# U_WE_BOX.net
KiCad netlist of a schematic drawn in EAGLE
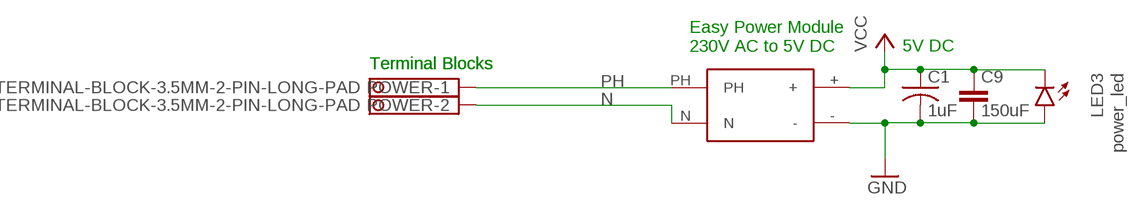
[diagram p0: schematic, sheet 1]
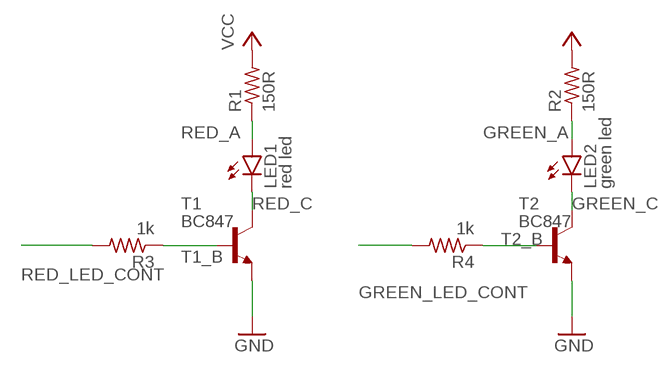
[diagram p1: schematic, sheet 2]
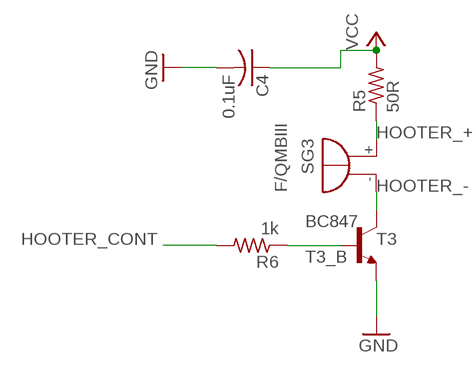
[diagram p2: schematic, sheet 3]
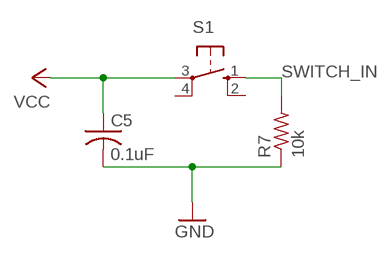
[diagram p3: schematic, sheet 4]
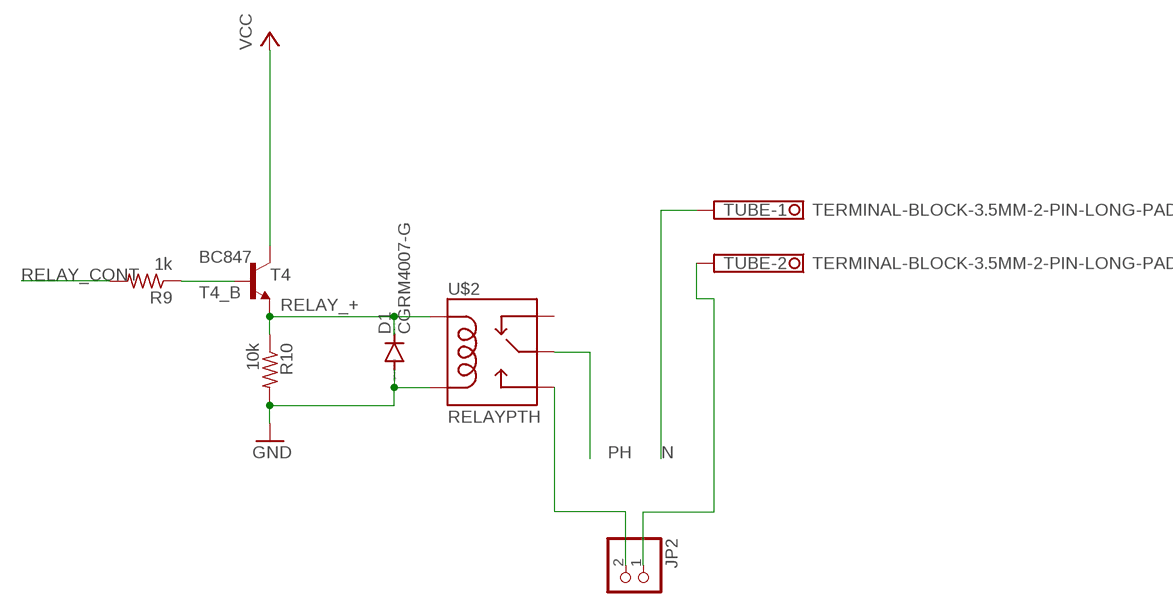
[diagram p4: schematic, sheet 5]
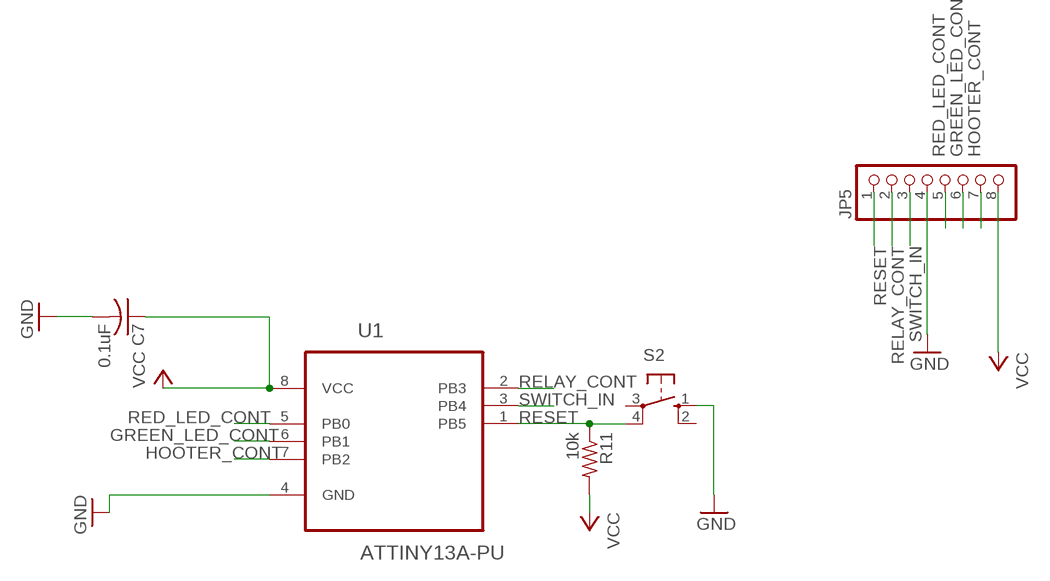
[diagram p5: schematic, sheet 6]

(export (version "E")
  (design (tool "Eeschema 10.0.6"))
  (components
    (comp (ref "D1")
      (value "CGRM4007-G")
      (footprint "eagle-import:SOD-123_MINI-SMA")
      (libsource (lib "eagle-import") (part "CGRM400-G7"))
    )
    (comp (ref "JP2")
      (value "PINHD-1X2")
      (footprint "eagle-import:1X02")
      (libsource (lib "eagle-import") (part "PINHD-1X2"))
    )
    (comp (ref "R9")
      (value "1k")
      (footprint "eagle-import:R1206")
      (libsource (lib "eagle-import") (part "R-US_R1206"))
    )
    (comp (ref "R10")
      (value "10k")
      (footprint "eagle-import:R1206")
      (libsource (lib "eagle-import") (part "R-US_R1206"))
    )
    (comp (ref "T4")
      (value "BC847")
      (footprint "eagle-import:SOT23")
      (libsource (lib "eagle-import") (part "BC847"))
    )
    (comp (ref "TUBE")
      (value "TERMINAL-BLOCK-3.5MM-2-PIN-LONG-PAD")
      (footprint "eagle-import:TERMINAL-BLOCK-2-PIN-3.5MM-LONG-PAD")
      (libsource (lib "eagle-import") (part "TERMINAL-BLOCK-3.5MM-2-PIN-LONG-PAD"))
    )
    (comp (ref "U$2")
      (value "RELAYPTH")
      (footprint "eagle-import:SRD-05VDC-SL-C")
      (libsource (lib "eagle-import") (part "RELAYPTH"))
    )
    (comp (ref "LED1")
      (value "red led")
      (footprint "eagle-import:CHIPLED_1206")
      (libsource (lib "eagle-import") (part "LEDCHIPLED_1206"))
    )
    (comp (ref "LED2")
      (value "green led")
      (footprint "eagle-import:CHIPLED_1206")
      (libsource (lib "eagle-import") (part "LEDCHIPLED_1206"))
    )
    (comp (ref "R1")
      (value "150R")
      (footprint "eagle-import:R1206")
      (libsource (lib "eagle-import") (part "R-US_R1206"))
    )
    (comp (ref "R2")
      (value "150R")
      (footprint "eagle-import:R1206")
      (libsource (lib "eagle-import") (part "R-US_R1206"))
    )
    (comp (ref "R3")
      (value "1k")
      (footprint "eagle-import:R1206")
      (libsource (lib "eagle-import") (part "R-US_R1206"))
    )
    (comp (ref "R4")
      (value "1k")
      (footprint "eagle-import:R1206")
      (libsource (lib "eagle-import") (part "R-US_R1206"))
    )
    (comp (ref "T1")
      (value "BC847")
      (footprint "eagle-import:SOT23")
      (libsource (lib "eagle-import") (part "BC847"))
    )
    (comp (ref "T2")
      (value "BC847")
      (footprint "eagle-import:SOT23")
      (libsource (lib "eagle-import") (part "BC847"))
    )
    (comp (ref "C5")
      (value "0.1uF")
      (footprint "eagle-import:C1206K")
      (libsource (lib "eagle-import") (part "C-USC1206K"))
    )
    (comp (ref "R7")
      (value "10k")
      (footprint "eagle-import:R1206")
      (libsource (lib "eagle-import") (part "R-US_R1206"))
    )
    (comp (ref "S1")
      (value "40-XX")
      (footprint "eagle-import:B3F-40XX")
      (fields (field (name "MF") "OMRON COMPONENTS USA") (field (name "MPN") "B3F-4000"))
      (libsource (lib "eagle-import") (part "40-XX"))
    )
    (comp (ref "C4")
      (value "0.1uF")
      (footprint "eagle-import:C1206K")
      (libsource (lib "eagle-import") (part "C-USC1206K"))
    )
    (comp (ref "R5")
      (value "50R")
      (footprint "eagle-import:R1206")
      (libsource (lib "eagle-import") (part "R-US_R1206"))
    )
    (comp (ref "R6")
      (value "1k")
      (footprint "eagle-import:R1206")
      (libsource (lib "eagle-import") (part "R-US_R1206"))
    )
    (comp (ref "SG3")
      (value "F/QMBIII")
      (footprint "eagle-import:F_QMBIII")
      (libsource (lib "eagle-import") (part "F/QMBIII"))
    )
    (comp (ref "T3")
      (value "BC847")
      (footprint "eagle-import:SOT23")
      (libsource (lib "eagle-import") (part "BC847"))
    )
    (comp (ref "C1")
      (value "1uF")
      (footprint "eagle-import:C1206K")
      (libsource (lib "eagle-import") (part "C-USC1206K"))
    )
    (comp (ref "C9")
      (value "150uF")
      (footprint "eagle-import:C5B5")
      (libsource (lib "eagle-import") (part "C5/5"))
    )
    (comp (ref "LED3")
      (value "power_led")
      (footprint "eagle-import:CHIPLED_1206")
      (libsource (lib "eagle-import") (part "LEDCHIPLED_1206"))
    )
    (comp (ref "POWER")
      (value "TERMINAL-BLOCK-3.5MM-2-PIN-LONG-PAD")
      (footprint "eagle-import:TERMINAL-BLOCK-2-PIN-3.5MM-LONG-PAD")
      (libsource (lib "eagle-import") (part "TERMINAL-BLOCK-3.5MM-2-PIN-LONG-PAD"))
    )
    (comp (ref "U2")
      (value "AC/DCCONVERTER")
      (footprint "eagle-import:ACDC")
      (libsource (lib "eagle-import") (part "AC/DCCONVERTER"))
    )
    (comp (ref "C7")
      (value "0.1uF")
      (footprint "eagle-import:C1206K")
      (libsource (lib "eagle-import") (part "C-USC1206K"))
    )
    (comp (ref "JP5")
      (value "PINHD-1X8")
      (footprint "eagle-import:1X08")
      (libsource (lib "eagle-import") (part "PINHD-1X8"))
    )
    (comp (ref "R11")
      (value "10k")
      (footprint "eagle-import:R1206")
      (libsource (lib "eagle-import") (part "R-US_R1206"))
    )
    (comp (ref "S2")
      (value "10-XX")
      (footprint "eagle-import:B3F-10XX")
      (fields (field (name "MPN") "B3F-1000"))
      (libsource (lib "eagle-import") (part "10-XX"))
    )
    (comp (ref "U1")
      (value "ATTINY13A-PU")
      (footprint "eagle-import:DIP254P762X533-8")
      (fields (field (name "MF") "Microchip"))
      (libsource (lib "eagle-import") (part "ATTINY13A-PU"))
    )
  )
  (nets
    (net (code "1") (name "GND") (class "Default")
      (node (ref "C1") (pin "2") (pinfunction "2_2") (pintype "passive"))
      (node (ref "C4") (pin "2") (pinfunction "2_2") (pintype "passive"))
      (node (ref "C5") (pin "2") (pinfunction "2_2") (pintype "passive"))
      (node (ref "C7") (pin "2") (pinfunction "2_2") (pintype "passive"))
      (node (ref "C9") (pin "2") (pinfunction "2_2") (pintype "passive"))
      (node (ref "D1") (pin "A") (pinfunction "A_A") (pintype "passive"))
      (node (ref "JP5") (pin "4") (pinfunction "4_4") (pintype "passive"))
      (node (ref "LED3") (pin "A") (pinfunction "A_A") (pintype "passive"))
      (node (ref "R10") (pin "2") (pinfunction "2_2") (pintype "passive"))
      (node (ref "R7") (pin "1") (pinfunction "1_1") (pintype "passive"))
      (node (ref "S2") (pin "1") (pinfunction "S_1") (pintype "passive"))
      (node (ref "T1") (pin "2") (pinfunction "E_2") (pintype "passive"))
      (node (ref "T2") (pin "2") (pinfunction "E_2") (pintype "passive"))
      (node (ref "T3") (pin "2") (pinfunction "E_2") (pintype "passive"))
      (node (ref "U$2") (pin "COIL0") (pinfunction "COIL0_COIL0") (pintype "bidirectional"))
      (node (ref "U1") (pin "4") (pinfunction "GND_4") (pintype "passive"))
      (node (ref "U2") (pin "-") (pinfunction "-_-") (pintype "bidirectional"))
    )
    (net (code "2") (name "GREEN_A") (class "Default")
      (node (ref "LED2") (pin "A") (pinfunction "A_A") (pintype "passive"))
      (node (ref "R2") (pin "1") (pinfunction "1_1") (pintype "passive"))
    )
    (net (code "3") (name "GREEN_C") (class "Default")
      (node (ref "LED2") (pin "C") (pinfunction "C_C") (pintype "passive"))
      (node (ref "T2") (pin "3") (pinfunction "C_3") (pintype "passive"))
    )
    (net (code "4") (name "GREEN_LED_CONT") (class "Default")
      (node (ref "JP5") (pin "6") (pinfunction "6_6") (pintype "passive"))
      (node (ref "R4") (pin "2") (pinfunction "2_2") (pintype "passive"))
      (node (ref "U1") (pin "6") (pinfunction "PB1_6") (pintype "bidirectional"))
    )
    (net (code "5") (name "HOOTER_+") (class "Default")
      (node (ref "R5") (pin "1") (pinfunction "1_1") (pintype "passive"))
      (node (ref "SG3") (pin "+") (pinfunction "-_+") (pintype "passive"))
    )
    (net (code "6") (name "HOOTER_-") (class "Default")
      (node (ref "SG3") (pin "-") (pinfunction "+_-") (pintype "passive"))
      (node (ref "T3") (pin "3") (pinfunction "C_3") (pintype "passive"))
    )
    (net (code "7") (name "HOOTER_CONT") (class "Default")
      (node (ref "JP5") (pin "7") (pinfunction "7_7") (pintype "passive"))
      (node (ref "R6") (pin "2") (pinfunction "2_2") (pintype "passive"))
      (node (ref "U1") (pin "7") (pinfunction "PB2_7") (pintype "bidirectional"))
    )
    (net (code "8") (name "N") (class "Default")
      (node (ref "POWER") (pin "2") (pinfunction "K_2") (pintype "passive"))
      (node (ref "TUBE") (pin "1") (pinfunction "K_1") (pintype "passive"))
      (node (ref "U2") (pin "N") (pinfunction "N_N") (pintype "bidirectional"))
    )
    (net (code "9") (name "Net-(JP2-Pad2)") (class "Default")
      (node (ref "JP2") (pin "2") (pinfunction "2_2") (pintype "passive"))
      (node (ref "U$2") (pin "SWOPEN") (pinfunction "SWOPEN_SWOPEN") (pintype "bidirectional"))
    )
    (net (code "10") (name "Net-(TUBEB-K)") (class "Default")
      (node (ref "JP2") (pin "1") (pinfunction "1_1") (pintype "passive"))
      (node (ref "TUBE") (pin "2") (pinfunction "K_2") (pintype "passive"))
    )
    (net (code "11") (name "PH") (class "Default")
      (node (ref "POWER") (pin "1") (pinfunction "K_1") (pintype "passive"))
      (node (ref "U$2") (pin "SWCOMMON") (pinfunction "SWCOMMON_SWCOMMON") (pintype "bidirectional"))
      (node (ref "U2") (pin "PH") (pinfunction "PH_PH") (pintype "bidirectional"))
    )
    (net (code "12") (name "RED_A") (class "Default")
      (node (ref "LED1") (pin "A") (pinfunction "A_A") (pintype "passive"))
      (node (ref "R1") (pin "1") (pinfunction "1_1") (pintype "passive"))
    )
    (net (code "13") (name "RED_C") (class "Default")
      (node (ref "LED1") (pin "C") (pinfunction "C_C") (pintype "passive"))
      (node (ref "T1") (pin "3") (pinfunction "C_3") (pintype "passive"))
    )
    (net (code "14") (name "RED_LED_CONT") (class "Default")
      (node (ref "JP5") (pin "5") (pinfunction "5_5") (pintype "passive"))
      (node (ref "R3") (pin "2") (pinfunction "2_2") (pintype "passive"))
      (node (ref "U1") (pin "5") (pinfunction "PB0_5") (pintype "bidirectional"))
    )
    (net (code "15") (name "RELAY_+") (class "Default")
      (node (ref "D1") (pin "C") (pinfunction "C_C") (pintype "passive"))
      (node (ref "R10") (pin "1") (pinfunction "1_1") (pintype "passive"))
      (node (ref "T4") (pin "2") (pinfunction "E_2") (pintype "passive"))
      (node (ref "U$2") (pin "COIL1") (pinfunction "COIL1_COIL1") (pintype "bidirectional"))
    )
    (net (code "16") (name "RELAY_CONT") (class "Default")
      (node (ref "JP5") (pin "2") (pinfunction "2_2") (pintype "passive"))
      (node (ref "R9") (pin "2") (pinfunction "2_2") (pintype "passive"))
      (node (ref "U1") (pin "2") (pinfunction "PB3_2") (pintype "bidirectional"))
    )
    (net (code "17") (name "RESET") (class "Default")
      (node (ref "JP5") (pin "1") (pinfunction "1_1") (pintype "passive"))
      (node (ref "R11") (pin "1") (pinfunction "1_1") (pintype "passive"))
      (node (ref "S2") (pin "4") (pinfunction "P1_4") (pintype "passive"))
      (node (ref "U1") (pin "1") (pinfunction "PB5_1") (pintype "bidirectional"))
    )
    (net (code "18") (name "SWITCH_IN") (class "Default")
      (node (ref "JP5") (pin "3") (pinfunction "3_3") (pintype "passive"))
      (node (ref "R7") (pin "2") (pinfunction "2_2") (pintype "passive"))
      (node (ref "S1") (pin "1") (pinfunction "S_1") (pintype "passive"))
      (node (ref "U1") (pin "3") (pinfunction "PB4_3") (pintype "bidirectional"))
    )
    (net (code "19") (name "T1_B") (class "Default")
      (node (ref "R3") (pin "1") (pinfunction "1_1") (pintype "passive"))
      (node (ref "T1") (pin "1") (pinfunction "B_1") (pintype "passive"))
    )
    (net (code "20") (name "T2_B") (class "Default")
      (node (ref "R4") (pin "1") (pinfunction "1_1") (pintype "passive"))
      (node (ref "T2") (pin "1") (pinfunction "B_1") (pintype "passive"))
    )
    (net (code "21") (name "T3_B") (class "Default")
      (node (ref "R6") (pin "1") (pinfunction "1_1") (pintype "passive"))
      (node (ref "T3") (pin "1") (pinfunction "B_1") (pintype "passive"))
    )
    (net (code "22") (name "T4_B") (class "Default")
      (node (ref "R9") (pin "1") (pinfunction "1_1") (pintype "passive"))
      (node (ref "T4") (pin "1") (pinfunction "B_1") (pintype "passive"))
    )
    (net (code "23") (name "VCC") (class "Default")
      (node (ref "C1") (pin "1") (pinfunction "1_1") (pintype "passive"))
      (node (ref "C4") (pin "1") (pinfunction "1_1") (pintype "passive"))
      (node (ref "C5") (pin "1") (pinfunction "1_1") (pintype "passive"))
      (node (ref "C7") (pin "1") (pinfunction "1_1") (pintype "passive"))
      (node (ref "C9") (pin "1") (pinfunction "1_1") (pintype "passive"))
      (node (ref "JP5") (pin "8") (pinfunction "8_8") (pintype "passive"))
      (node (ref "LED3") (pin "C") (pinfunction "C_C") (pintype "passive"))
      (node (ref "R1") (pin "2") (pinfunction "2_2") (pintype "passive"))
      (node (ref "R11") (pin "2") (pinfunction "2_2") (pintype "passive"))
      (node (ref "R2") (pin "2") (pinfunction "2_2") (pintype "passive"))
      (node (ref "R5") (pin "2") (pinfunction "2_2") (pintype "passive"))
      (node (ref "S1") (pin "3") (pinfunction "P_3") (pintype "passive"))
      (node (ref "T4") (pin "3") (pinfunction "C_3") (pintype "passive"))
      (node (ref "U1") (pin "8") (pinfunction "VCC_8") (pintype "power_in"))
      (node (ref "U2") (pin "+") (pinfunction "+_+") (pintype "bidirectional"))
    )
    (net (code "24") (name "unconnected-(S1-P1-Pad4)") (class "Default")
      (node (ref "S1") (pin "4") (pinfunction "P1_4") (pintype "passive"))
    )
    (net (code "25") (name "unconnected-(S1-S1-Pad2)") (class "Default")
      (node (ref "S1") (pin "2") (pinfunction "S1_2") (pintype "passive"))
    )
    (net (code "26") (name "unconnected-(S2-P-Pad3)") (class "Default")
      (node (ref "S2") (pin "3") (pinfunction "P_3") (pintype "passive"))
    )
    (net (code "27") (name "unconnected-(S2-S1-Pad2)") (class "Default")
      (node (ref "S2") (pin "2") (pinfunction "S1_2") (pintype "passive"))
    )
    (net (code "28") (name "unconnected-(U$2-SWCLOSE-PadSWCLOSED)") (class "Default")
      (node (ref "U$2") (pin "SWCLOSED") (pinfunction "SWCLOSE_SWCLOSED") (pintype "bidirectional"))
    )
  )
)
